# stepper_step_up.net
KiCad netlist of a schematic drawn in EAGLE
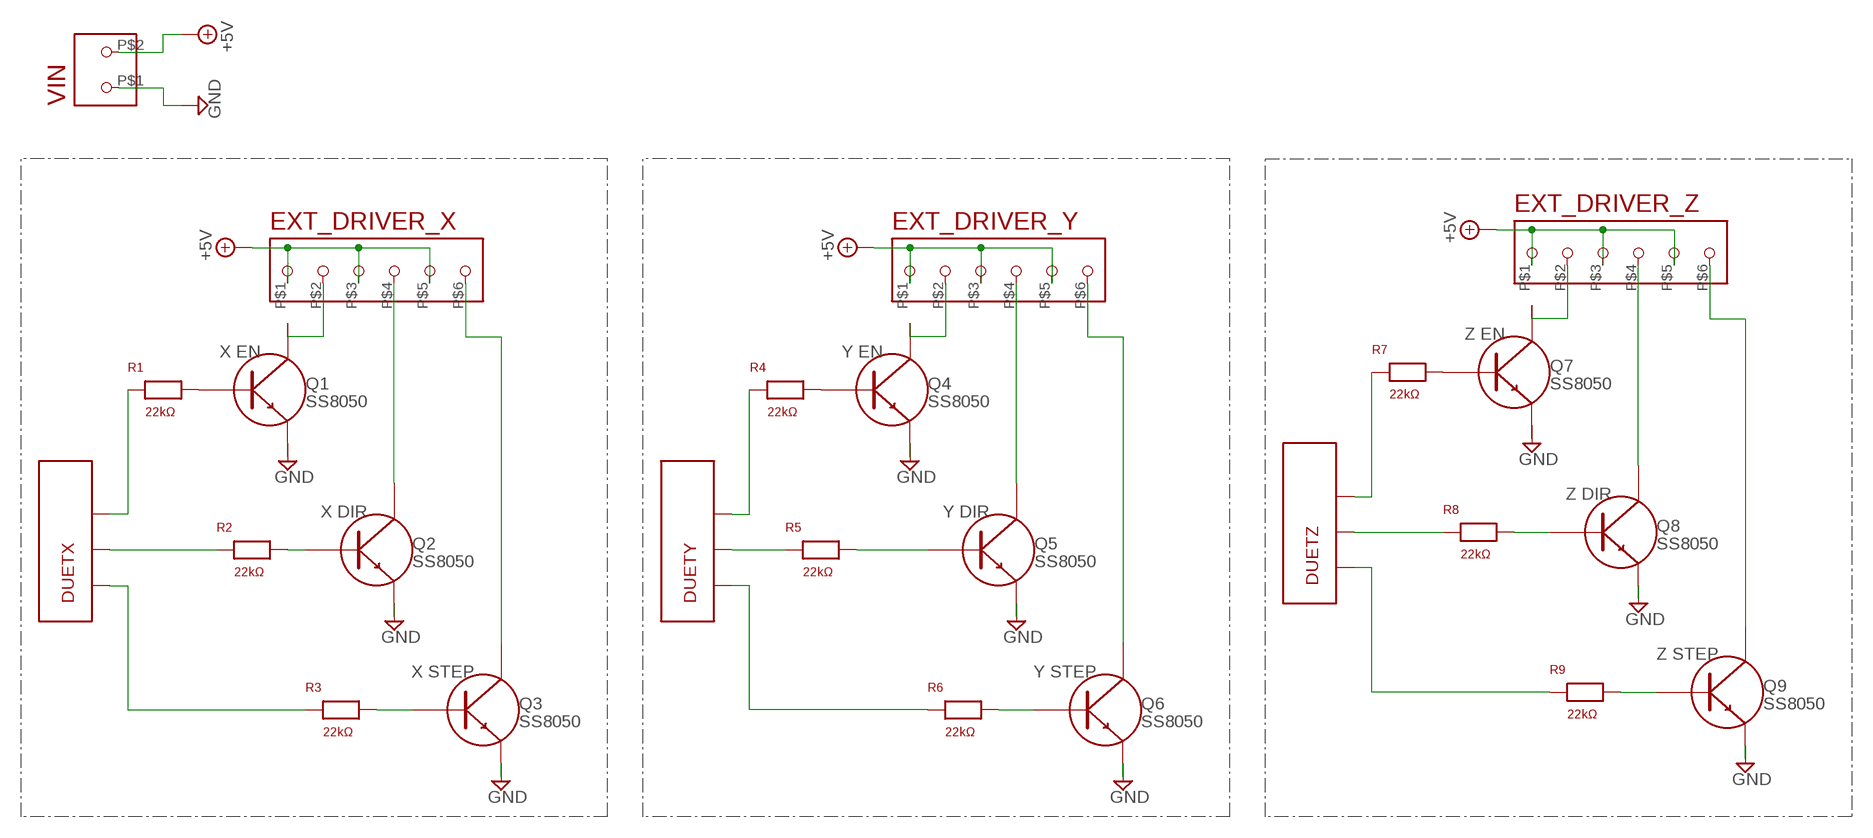
[diagram p0: schematic, sheet 1]

(export (version "E")
  (design (tool "Eeschema 10.0.6"))
  (components
    (comp (ref "DUETX")
      (value "BKL_3XPINHEAD")
      (footprint "eagle-import:BKL_3XPINHEAD")
      (libsource (lib "eagle-import") (part "BKL_3XPINHEAD"))
    )
    (comp (ref "DUETY")
      (value "BKL_3XPINHEAD")
      (footprint "eagle-import:BKL_3XPINHEAD")
      (libsource (lib "eagle-import") (part "BKL_3XPINHEAD"))
    )
    (comp (ref "DUETZ")
      (value "BKL_3XPINHEAD")
      (footprint "eagle-import:BKL_3XPINHEAD")
      (libsource (lib "eagle-import") (part "BKL_3XPINHEAD"))
    )
    (comp (ref "EXT_DRIVER_X")
      (value "SCREW_X6")
      (footprint "eagle-import:SCREW_X6")
      (libsource (lib "eagle-import") (part "SCREW_X6"))
    )
    (comp (ref "EXT_DRIVER_Y")
      (value "SCREW_X6")
      (footprint "eagle-import:SCREW_X6")
      (libsource (lib "eagle-import") (part "SCREW_X6"))
    )
    (comp (ref "EXT_DRIVER_Z")
      (value "SCREW_X6")
      (footprint "eagle-import:SCREW_X6")
      (libsource (lib "eagle-import") (part "SCREW_X6"))
    )
    (comp (ref "Q1")
      (value "SS8050")
      (footprint "eagle-import:NPN_SS8050")
      (libsource (lib "eagle-import") (part "NPN_SS8050"))
    )
    (comp (ref "Q2")
      (value "SS8050")
      (footprint "eagle-import:NPN_SS8050")
      (libsource (lib "eagle-import") (part "NPN_SS8050"))
    )
    (comp (ref "Q3")
      (value "SS8050")
      (footprint "eagle-import:NPN_SS8050")
      (libsource (lib "eagle-import") (part "NPN_SS8050"))
    )
    (comp (ref "Q4")
      (value "SS8050")
      (footprint "eagle-import:NPN_SS8050")
      (libsource (lib "eagle-import") (part "NPN_SS8050"))
    )
    (comp (ref "Q5")
      (value "SS8050")
      (footprint "eagle-import:NPN_SS8050")
      (libsource (lib "eagle-import") (part "NPN_SS8050"))
    )
    (comp (ref "Q6")
      (value "SS8050")
      (footprint "eagle-import:NPN_SS8050")
      (libsource (lib "eagle-import") (part "NPN_SS8050"))
    )
    (comp (ref "Q7")
      (value "SS8050")
      (footprint "eagle-import:NPN_SS8050")
      (libsource (lib "eagle-import") (part "NPN_SS8050"))
    )
    (comp (ref "Q8")
      (value "SS8050")
      (footprint "eagle-import:NPN_SS8050")
      (libsource (lib "eagle-import") (part "NPN_SS8050"))
    )
    (comp (ref "Q9")
      (value "SS8050")
      (footprint "eagle-import:NPN_SS8050")
      (libsource (lib "eagle-import") (part "NPN_SS8050"))
    )
    (comp (ref "R1")
      (value "22kΩ")
      (footprint "eagle-import:VERT_RES")
      (libsource (lib "eagle-import") (part "VERT_RES"))
    )
    (comp (ref "R2")
      (value "22kΩ")
      (footprint "eagle-import:VERT_RES")
      (libsource (lib "eagle-import") (part "VERT_RES"))
    )
    (comp (ref "R3")
      (value "22kΩ")
      (footprint "eagle-import:VERT_RES")
      (libsource (lib "eagle-import") (part "VERT_RES"))
    )
    (comp (ref "R4")
      (value "22kΩ")
      (footprint "eagle-import:VERT_RES")
      (libsource (lib "eagle-import") (part "VERT_RES"))
    )
    (comp (ref "R5")
      (value "22kΩ")
      (footprint "eagle-import:VERT_RES")
      (libsource (lib "eagle-import") (part "VERT_RES"))
    )
    (comp (ref "R6")
      (value "22kΩ")
      (footprint "eagle-import:VERT_RES")
      (libsource (lib "eagle-import") (part "VERT_RES"))
    )
    (comp (ref "R7")
      (value "22kΩ")
      (footprint "eagle-import:VERT_RES")
      (libsource (lib "eagle-import") (part "VERT_RES"))
    )
    (comp (ref "R8")
      (value "22kΩ")
      (footprint "eagle-import:VERT_RES")
      (libsource (lib "eagle-import") (part "VERT_RES"))
    )
    (comp (ref "R9")
      (value "22kΩ")
      (footprint "eagle-import:VERT_RES")
      (libsource (lib "eagle-import") (part "VERT_RES"))
    )
    (comp (ref "VIN")
      (value "SCREW_X2")
      (footprint "eagle-import:SCREW_X2")
      (libsource (lib "eagle-import") (part "SCREW_X2"))
    )
  )
  (nets
    (net (code "1") (name "+5V") (class "Default")
      (node (ref "EXT_DRIVER_X") (pin "P$1") (pinfunction "P$1_P$1") (pintype "bidirectional"))
      (node (ref "EXT_DRIVER_X") (pin "P$3") (pinfunction "P$3_P$3") (pintype "bidirectional"))
      (node (ref "EXT_DRIVER_X") (pin "P$5") (pinfunction "P$5_P$5") (pintype "bidirectional"))
      (node (ref "EXT_DRIVER_Y") (pin "P$1") (pinfunction "P$1_P$1") (pintype "bidirectional"))
      (node (ref "EXT_DRIVER_Y") (pin "P$3") (pinfunction "P$3_P$3") (pintype "bidirectional"))
      (node (ref "EXT_DRIVER_Y") (pin "P$5") (pinfunction "P$5_P$5") (pintype "bidirectional"))
      (node (ref "EXT_DRIVER_Z") (pin "P$1") (pinfunction "P$1_P$1") (pintype "bidirectional"))
      (node (ref "EXT_DRIVER_Z") (pin "P$3") (pinfunction "P$3_P$3") (pintype "bidirectional"))
      (node (ref "EXT_DRIVER_Z") (pin "P$5") (pinfunction "P$5_P$5") (pintype "bidirectional"))
      (node (ref "VIN") (pin "P$2") (pinfunction "P$2_P$2") (pintype "bidirectional"))
    )
    (net (code "2") (name "GND") (class "Default")
      (node (ref "Q1") (pin "E") (pinfunction "E_E") (pintype "bidirectional"))
      (node (ref "Q2") (pin "E") (pinfunction "E_E") (pintype "bidirectional"))
      (node (ref "Q3") (pin "E") (pinfunction "E_E") (pintype "bidirectional"))
      (node (ref "Q4") (pin "E") (pinfunction "E_E") (pintype "bidirectional"))
      (node (ref "Q5") (pin "E") (pinfunction "E_E") (pintype "bidirectional"))
      (node (ref "Q6") (pin "E") (pinfunction "E_E") (pintype "bidirectional"))
      (node (ref "Q7") (pin "E") (pinfunction "E_E") (pintype "bidirectional"))
      (node (ref "Q8") (pin "E") (pinfunction "E_E") (pintype "bidirectional"))
      (node (ref "Q9") (pin "E") (pinfunction "E_E") (pintype "bidirectional"))
      (node (ref "VIN") (pin "P$1") (pinfunction "P$1_P$1") (pintype "bidirectional"))
    )
    (net (code "3") (name "Net-(DUETX-PadP$1)") (class "Default")
      (node (ref "DUETX") (pin "P$1") (pinfunction "P$1_P$1") (pintype "bidirectional"))
      (node (ref "R3") (pin "P$1") (pinfunction "P$1_P$1") (pintype "bidirectional"))
    )
    (net (code "4") (name "Net-(DUETX-PadP$2)") (class "Default")
      (node (ref "DUETX") (pin "P$2") (pinfunction "P$2_P$2") (pintype "bidirectional"))
      (node (ref "R2") (pin "P$1") (pinfunction "P$1_P$1") (pintype "bidirectional"))
    )
    (net (code "5") (name "Net-(DUETX-PadP$3)") (class "Default")
      (node (ref "DUETX") (pin "P$3") (pinfunction "P$3_P$3") (pintype "bidirectional"))
      (node (ref "R1") (pin "P$1") (pinfunction "P$1_P$1") (pintype "bidirectional"))
    )
    (net (code "6") (name "Net-(DUETY-PadP$1)") (class "Default")
      (node (ref "DUETY") (pin "P$1") (pinfunction "P$1_P$1") (pintype "bidirectional"))
      (node (ref "R6") (pin "P$1") (pinfunction "P$1_P$1") (pintype "bidirectional"))
    )
    (net (code "7") (name "Net-(DUETY-PadP$2)") (class "Default")
      (node (ref "DUETY") (pin "P$2") (pinfunction "P$2_P$2") (pintype "bidirectional"))
      (node (ref "R5") (pin "P$1") (pinfunction "P$1_P$1") (pintype "bidirectional"))
    )
    (net (code "8") (name "Net-(DUETY-PadP$3)") (class "Default")
      (node (ref "DUETY") (pin "P$3") (pinfunction "P$3_P$3") (pintype "bidirectional"))
      (node (ref "R4") (pin "P$1") (pinfunction "P$1_P$1") (pintype "bidirectional"))
    )
    (net (code "9") (name "Net-(DUETZ-PadP$1)") (class "Default")
      (node (ref "DUETZ") (pin "P$1") (pinfunction "P$1_P$1") (pintype "bidirectional"))
      (node (ref "R9") (pin "P$1") (pinfunction "P$1_P$1") (pintype "bidirectional"))
    )
    (net (code "10") (name "Net-(DUETZ-PadP$2)") (class "Default")
      (node (ref "DUETZ") (pin "P$2") (pinfunction "P$2_P$2") (pintype "bidirectional"))
      (node (ref "R8") (pin "P$1") (pinfunction "P$1_P$1") (pintype "bidirectional"))
    )
    (net (code "11") (name "Net-(DUETZ-PadP$3)") (class "Default")
      (node (ref "DUETZ") (pin "P$3") (pinfunction "P$3_P$3") (pintype "bidirectional"))
      (node (ref "R7") (pin "P$1") (pinfunction "P$1_P$1") (pintype "bidirectional"))
    )
    (net (code "12") (name "Net-(EXT_DRIVER_X-PadP$2)") (class "Default")
      (node (ref "EXT_DRIVER_X") (pin "P$2") (pinfunction "P$2_P$2") (pintype "bidirectional"))
      (node (ref "Q1") (pin "C") (pinfunction "C_C") (pintype "bidirectional"))
    )
    (net (code "13") (name "Net-(EXT_DRIVER_X-PadP$4)") (class "Default")
      (node (ref "EXT_DRIVER_X") (pin "P$4") (pinfunction "P$4_P$4") (pintype "bidirectional"))
      (node (ref "Q2") (pin "C") (pinfunction "C_C") (pintype "bidirectional"))
    )
    (net (code "14") (name "Net-(EXT_DRIVER_X-PadP$6)") (class "Default")
      (node (ref "EXT_DRIVER_X") (pin "P$6") (pinfunction "P$6_P$6") (pintype "bidirectional"))
      (node (ref "Q3") (pin "C") (pinfunction "C_C") (pintype "bidirectional"))
    )
    (net (code "15") (name "Net-(EXT_DRIVER_Y-PadP$2)") (class "Default")
      (node (ref "EXT_DRIVER_Y") (pin "P$2") (pinfunction "P$2_P$2") (pintype "bidirectional"))
      (node (ref "Q4") (pin "C") (pinfunction "C_C") (pintype "bidirectional"))
    )
    (net (code "16") (name "Net-(EXT_DRIVER_Y-PadP$4)") (class "Default")
      (node (ref "EXT_DRIVER_Y") (pin "P$4") (pinfunction "P$4_P$4") (pintype "bidirectional"))
      (node (ref "Q5") (pin "C") (pinfunction "C_C") (pintype "bidirectional"))
    )
    (net (code "17") (name "Net-(EXT_DRIVER_Y-PadP$6)") (class "Default")
      (node (ref "EXT_DRIVER_Y") (pin "P$6") (pinfunction "P$6_P$6") (pintype "bidirectional"))
      (node (ref "Q6") (pin "C") (pinfunction "C_C") (pintype "bidirectional"))
    )
    (net (code "18") (name "Net-(EXT_DRIVER_Z-PadP$2)") (class "Default")
      (node (ref "EXT_DRIVER_Z") (pin "P$2") (pinfunction "P$2_P$2") (pintype "bidirectional"))
      (node (ref "Q7") (pin "C") (pinfunction "C_C") (pintype "bidirectional"))
    )
    (net (code "19") (name "Net-(EXT_DRIVER_Z-PadP$4)") (class "Default")
      (node (ref "EXT_DRIVER_Z") (pin "P$4") (pinfunction "P$4_P$4") (pintype "bidirectional"))
      (node (ref "Q8") (pin "C") (pinfunction "C_C") (pintype "bidirectional"))
    )
    (net (code "20") (name "Net-(EXT_DRIVER_Z-PadP$6)") (class "Default")
      (node (ref "EXT_DRIVER_Z") (pin "P$6") (pinfunction "P$6_P$6") (pintype "bidirectional"))
      (node (ref "Q9") (pin "C") (pinfunction "C_C") (pintype "bidirectional"))
    )
    (net (code "21") (name "Net-(Q1-PadB)") (class "Default")
      (node (ref "Q1") (pin "B") (pinfunction "B_B") (pintype "bidirectional"))
      (node (ref "R1") (pin "P$2") (pinfunction "P$2_P$2") (pintype "bidirectional"))
    )
    (net (code "22") (name "Net-(Q2-PadB)") (class "Default")
      (node (ref "Q2") (pin "B") (pinfunction "B_B") (pintype "bidirectional"))
      (node (ref "R2") (pin "P$2") (pinfunction "P$2_P$2") (pintype "bidirectional"))
    )
    (net (code "23") (name "Net-(Q3-PadB)") (class "Default")
      (node (ref "Q3") (pin "B") (pinfunction "B_B") (pintype "bidirectional"))
      (node (ref "R3") (pin "P$2") (pinfunction "P$2_P$2") (pintype "bidirectional"))
    )
    (net (code "24") (name "Net-(Q4-PadB)") (class "Default")
      (node (ref "Q4") (pin "B") (pinfunction "B_B") (pintype "bidirectional"))
      (node (ref "R4") (pin "P$2") (pinfunction "P$2_P$2") (pintype "bidirectional"))
    )
    (net (code "25") (name "Net-(Q5-PadB)") (class "Default")
      (node (ref "Q5") (pin "B") (pinfunction "B_B") (pintype "bidirectional"))
      (node (ref "R5") (pin "P$2") (pinfunction "P$2_P$2") (pintype "bidirectional"))
    )
    (net (code "26") (name "Net-(Q6-PadB)") (class "Default")
      (node (ref "Q6") (pin "B") (pinfunction "B_B") (pintype "bidirectional"))
      (node (ref "R6") (pin "P$2") (pinfunction "P$2_P$2") (pintype "bidirectional"))
    )
    (net (code "27") (name "Net-(Q7-PadB)") (class "Default")
      (node (ref "Q7") (pin "B") (pinfunction "B_B") (pintype "bidirectional"))
      (node (ref "R7") (pin "P$2") (pinfunction "P$2_P$2") (pintype "bidirectional"))
    )
    (net (code "28") (name "Net-(Q8-PadB)") (class "Default")
      (node (ref "Q8") (pin "B") (pinfunction "B_B") (pintype "bidirectional"))
      (node (ref "R8") (pin "P$2") (pinfunction "P$2_P$2") (pintype "bidirectional"))
    )
    (net (code "29") (name "Net-(Q9-PadB)") (class "Default")
      (node (ref "Q9") (pin "B") (pinfunction "B_B") (pintype "bidirectional"))
      (node (ref "R9") (pin "P$2") (pinfunction "P$2_P$2") (pintype "bidirectional"))
    )
  )
)
